# 18_Power_Management.net
KiCad netlist of a schematic drawn in Altium Designer
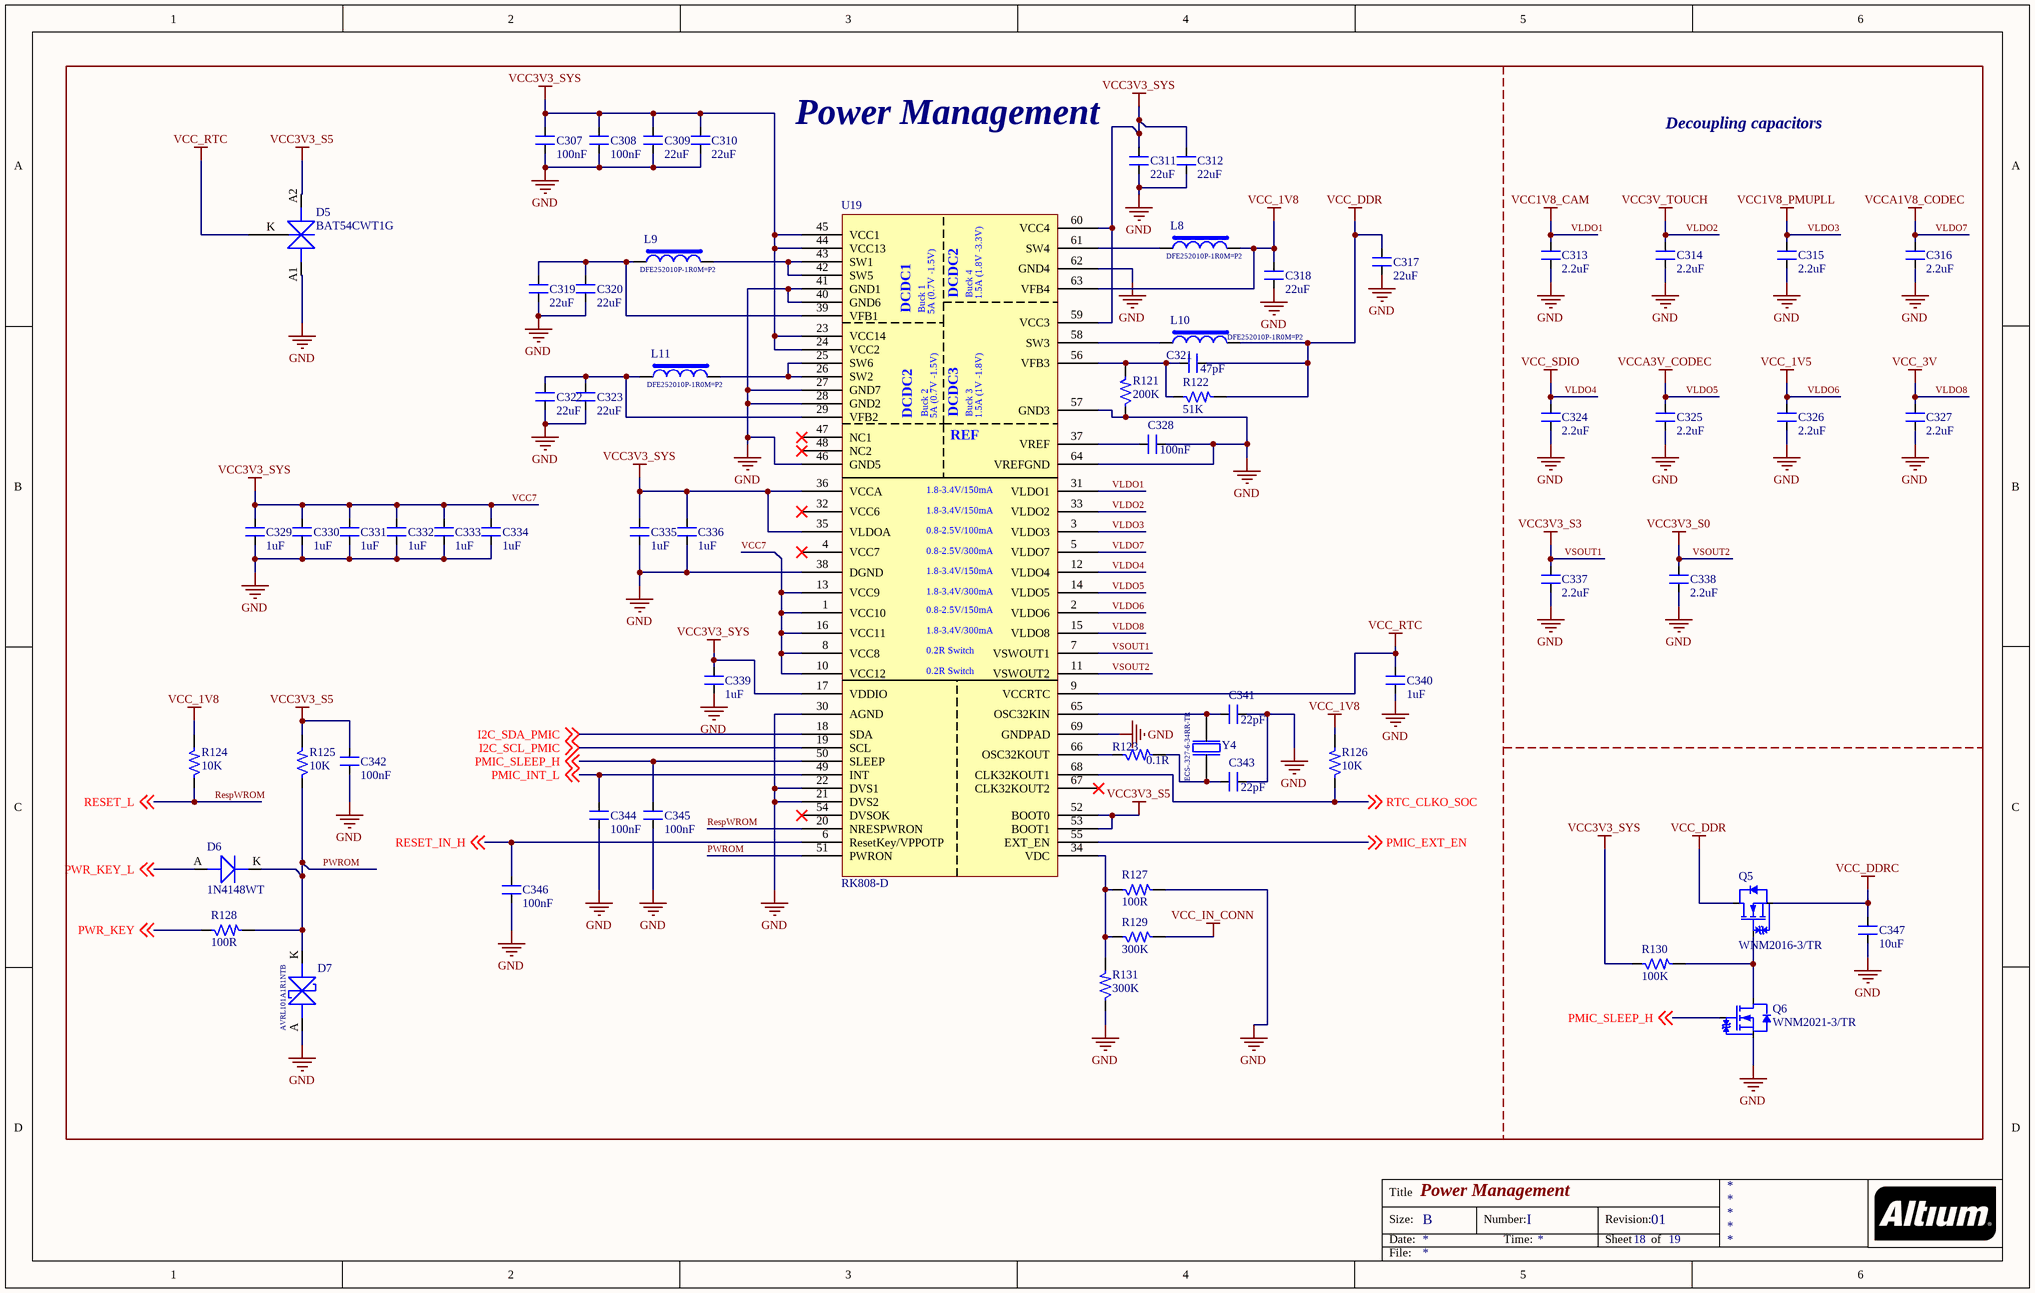
[diagram p0: [18] Power_Management.SchDoc]

(export (version "E")
  (design (tool "Eeschema 10.0.6"))
  (components
    (comp (ref "C307")
      (value "100nF")
      (footprint "CAP_0402")
      (description "0.1µF ±10% 25V Ceramic Capacitor X7R 0402 (1005 Metric)")
      (fields
        (field (name "MANUFACTURER") "Walsin Technology Corporation")
        (field (name "MANUFACTURER PART NUMBER") "0402B104K250CT")
      )
      (libsource (lib "EsteemPCB_SOM_Course_intlib") (part "CAP_100nF-25V-10%-0402"))
    )
    (comp (ref "C308")
      (value "100nF")
      (footprint "CAP_0402")
      (description "0.1µF ±10% 25V Ceramic Capacitor X7R 0402 (1005 Metric)")
      (fields
        (field (name "MANUFACTURER") "Walsin Technology Corporation")
        (field (name "MANUFACTURER PART NUMBER") "0402B104K250CT")
      )
      (libsource (lib "EsteemPCB_SOM_Course_intlib") (part "CAP_100nF-25V-10%-0402"))
    )
    (comp (ref "C309")
      (value "22uF")
      (footprint "CAP_0603")
      (description "22µF ±20% 10V Ceramic Capacitor X5R 0603 (1608 Metric)")
      (fields
        (field (name "MANUFACTURER") "Murata Electronics")
        (field (name "MANUFACTURER PART NUMBER") "GRM188R61A226ME15D")
      )
      (libsource (lib "EsteemPCB_SOM_Course_intlib") (part "CAP_22uF-10V-20%-0603"))
    )
    (comp (ref "C310")
      (value "22uF")
      (footprint "CAP_0603")
      (description "22µF ±20% 10V Ceramic Capacitor X5R 0603 (1608 Metric)")
      (fields
        (field (name "MANUFACTURER") "Murata Electronics")
        (field (name "MANUFACTURER PART NUMBER") "GRM188R61A226ME15D")
      )
      (libsource (lib "EsteemPCB_SOM_Course_intlib") (part "CAP_22uF-10V-20%-0603"))
    )
    (comp (ref "C311")
      (value "22uF")
      (footprint "CAP_0603")
      (description "22µF ±20% 10V Ceramic Capacitor X5R 0603 (1608 Metric)")
      (fields
        (field (name "MANUFACTURER") "Murata Electronics")
        (field (name "MANUFACTURER PART NUMBER") "GRM188R61A226ME15D")
      )
      (libsource (lib "EsteemPCB_SOM_Course_intlib") (part "CAP_22uF-10V-20%-0603"))
    )
    (comp (ref "C312")
      (value "22uF")
      (footprint "CAP_0603")
      (description "22µF ±20% 10V Ceramic Capacitor X5R 0603 (1608 Metric)")
      (fields
        (field (name "MANUFACTURER") "Murata Electronics")
        (field (name "MANUFACTURER PART NUMBER") "GRM188R61A226ME15D")
      )
      (libsource (lib "EsteemPCB_SOM_Course_intlib") (part "CAP_22uF-10V-20%-0603"))
    )
    (comp (ref "C313")
      (value "2.2uF")
      (footprint "CAP_0402")
      (description "2.2µF ±10% 10V Ceramic Capacitor X5R 0402 (1005 Metric)")
      (fields
        (field (name "MANUFACTURER") "Murata Electronics")
        (field (name "MANUFACTURER PART NUMBER") "GRM155R61A225KE95D")
      )
      (libsource (lib "EsteemPCB_SOM_Course_intlib") (part "CAP_2.2uF-10V-10%-0402"))
    )
    (comp (ref "C314")
      (value "2.2uF")
      (footprint "CAP_0402")
      (description "2.2µF ±10% 10V Ceramic Capacitor X5R 0402 (1005 Metric)")
      (fields
        (field (name "MANUFACTURER") "Murata Electronics")
        (field (name "MANUFACTURER PART NUMBER") "GRM155R61A225KE95D")
      )
      (libsource (lib "EsteemPCB_SOM_Course_intlib") (part "CAP_2.2uF-10V-10%-0402"))
    )
    (comp (ref "C315")
      (value "2.2uF")
      (footprint "CAP_0402")
      (description "2.2µF ±10% 10V Ceramic Capacitor X5R 0402 (1005 Metric)")
      (fields
        (field (name "MANUFACTURER") "Murata Electronics")
        (field (name "MANUFACTURER PART NUMBER") "GRM155R61A225KE95D")
      )
      (libsource (lib "EsteemPCB_SOM_Course_intlib") (part "CAP_2.2uF-10V-10%-0402"))
    )
    (comp (ref "C316")
      (value "2.2uF")
      (footprint "CAP_0402")
      (description "2.2µF ±10% 10V Ceramic Capacitor X5R 0402 (1005 Metric)")
      (fields
        (field (name "MANUFACTURER") "Murata Electronics")
        (field (name "MANUFACTURER PART NUMBER") "GRM155R61A225KE95D")
      )
      (libsource (lib "EsteemPCB_SOM_Course_intlib") (part "CAP_2.2uF-10V-10%-0402"))
    )
    (comp (ref "C317")
      (value "22uF")
      (footprint "CAP_0603")
      (description "22µF ±20% 10V Ceramic Capacitor X5R 0603 (1608 Metric)")
      (fields
        (field (name "MANUFACTURER") "Murata Electronics")
        (field (name "MANUFACTURER PART NUMBER") "GRM188R61A226ME15D")
      )
      (libsource (lib "EsteemPCB_SOM_Course_intlib") (part "CAP_22uF-10V-20%-0603"))
    )
    (comp (ref "C318")
      (value "22uF")
      (footprint "CAP_0603")
      (description "22µF ±20% 10V Ceramic Capacitor X5R 0603 (1608 Metric)")
      (fields
        (field (name "MANUFACTURER") "Murata Electronics")
        (field (name "MANUFACTURER PART NUMBER") "GRM188R61A226ME15D")
      )
      (libsource (lib "EsteemPCB_SOM_Course_intlib") (part "CAP_22uF-10V-20%-0603"))
    )
    (comp (ref "C319")
      (value "22uF")
      (footprint "CAP_0603")
      (description "22µF ±20% 10V Ceramic Capacitor X5R 0603 (1608 Metric)")
      (fields
        (field (name "MANUFACTURER") "Murata Electronics")
        (field (name "MANUFACTURER PART NUMBER") "GRM188R61A226ME15D")
      )
      (libsource (lib "EsteemPCB_SOM_Course_intlib") (part "CAP_22uF-10V-20%-0603"))
    )
    (comp (ref "C320")
      (value "22uF")
      (footprint "CAP_0603")
      (description "22µF ±20% 10V Ceramic Capacitor X5R 0603 (1608 Metric)")
      (fields
        (field (name "MANUFACTURER") "Murata Electronics")
        (field (name "MANUFACTURER PART NUMBER") "GRM188R61A226ME15D")
      )
      (libsource (lib "EsteemPCB_SOM_Course_intlib") (part "CAP_22uF-10V-20%-0603"))
    )
    (comp (ref "C321")
      (value "47pF")
      (footprint "CAP_0402")
      (description "47pF ±10% 10V Ceramic Capacitor C0G, NP0 0402 (1005 Metric)")
      (fields
        (field (name "MANUFACTURER") "KEMET")
        (field (name "MANUFACTURER PART NUMBER") "C0402C470K8GAC7867")
      )
      (libsource (lib "EsteemPCB_SOM_Course_intlib") (part "CAP_47pF-10V-10%-0402"))
    )
    (comp (ref "C322")
      (value "22uF")
      (footprint "CAP_0603")
      (description "22µF ±20% 10V Ceramic Capacitor X5R 0603 (1608 Metric)")
      (fields
        (field (name "MANUFACTURER") "Murata Electronics")
        (field (name "MANUFACTURER PART NUMBER") "GRM188R61A226ME15D")
      )
      (libsource (lib "EsteemPCB_SOM_Course_intlib") (part "CAP_22uF-10V-20%-0603"))
    )
    (comp (ref "C323")
      (value "22uF")
      (footprint "CAP_0603")
      (description "22µF ±20% 10V Ceramic Capacitor X5R 0603 (1608 Metric)")
      (fields
        (field (name "MANUFACTURER") "Murata Electronics")
        (field (name "MANUFACTURER PART NUMBER") "GRM188R61A226ME15D")
      )
      (libsource (lib "EsteemPCB_SOM_Course_intlib") (part "CAP_22uF-10V-20%-0603"))
    )
    (comp (ref "C324")
      (value "2.2uF")
      (footprint "CAP_0402")
      (description "2.2µF ±10% 10V Ceramic Capacitor X5R 0402 (1005 Metric)")
      (fields
        (field (name "MANUFACTURER") "Murata Electronics")
        (field (name "MANUFACTURER PART NUMBER") "GRM155R61A225KE95D")
      )
      (libsource (lib "EsteemPCB_SOM_Course_intlib") (part "CAP_2.2uF-10V-10%-0402"))
    )
    (comp (ref "C325")
      (value "2.2uF")
      (footprint "CAP_0402")
      (description "2.2µF ±10% 10V Ceramic Capacitor X5R 0402 (1005 Metric)")
      (fields
        (field (name "MANUFACTURER") "Murata Electronics")
        (field (name "MANUFACTURER PART NUMBER") "GRM155R61A225KE95D")
      )
      (libsource (lib "EsteemPCB_SOM_Course_intlib") (part "CAP_2.2uF-10V-10%-0402"))
    )
    (comp (ref "C326")
      (value "2.2uF")
      (footprint "CAP_0402")
      (description "2.2µF ±10% 10V Ceramic Capacitor X5R 0402 (1005 Metric)")
      (fields
        (field (name "MANUFACTURER") "Murata Electronics")
        (field (name "MANUFACTURER PART NUMBER") "GRM155R61A225KE95D")
      )
      (libsource (lib "EsteemPCB_SOM_Course_intlib") (part "CAP_2.2uF-10V-10%-0402"))
    )
    (comp (ref "C327")
      (value "2.2uF")
      (footprint "CAP_0402")
      (description "2.2µF ±10% 10V Ceramic Capacitor X5R 0402 (1005 Metric)")
      (fields
        (field (name "MANUFACTURER") "Murata Electronics")
        (field (name "MANUFACTURER PART NUMBER") "GRM155R61A225KE95D")
      )
      (libsource (lib "EsteemPCB_SOM_Course_intlib") (part "CAP_2.2uF-10V-10%-0402"))
    )
    (comp (ref "C328")
      (value "100nF")
      (footprint "CAP_0402")
      (description "0.1µF ±10% 10V Ceramic Capacitor X7R 0402 (1005 Metric)")
      (fields
        (field (name "MANUFACTURER") "Yageo")
        (field (name "MANUFACTURER PART NUMBER") "CC0402KRX7R6BB104")
      )
      (libsource (lib "EsteemPCB_SOM_Course_intlib") (part "CAP_100nF-10V-10%-0402"))
    )
    (comp (ref "C329")
      (value "1uF")
      (footprint "CAP_0402")
      (description "1µF ±10% 10V Ceramic Capacitor X6S 0402 (1005 Metric)")
      (fields
        (field (name "MANUFACTURER") "Murata Electronics")
        (field (name "MANUFACTURER PART NUMBER") "GRT155C81A105KE01D")
      )
      (libsource (lib "EsteemPCB_SOM_Course_intlib") (part "CAP_1uF-10V-10%-0402"))
    )
    (comp (ref "C330")
      (value "1uF")
      (footprint "CAP_0402")
      (description "1µF ±10% 10V Ceramic Capacitor X6S 0402 (1005 Metric)")
      (fields
        (field (name "MANUFACTURER") "Murata Electronics")
        (field (name "MANUFACTURER PART NUMBER") "GRT155C81A105KE01D")
      )
      (libsource (lib "EsteemPCB_SOM_Course_intlib") (part "CAP_1uF-10V-10%-0402"))
    )
    (comp (ref "C331")
      (value "1uF")
      (footprint "CAP_0402")
      (description "1µF ±10% 10V Ceramic Capacitor X6S 0402 (1005 Metric)")
      (fields
        (field (name "MANUFACTURER") "Murata Electronics")
        (field (name "MANUFACTURER PART NUMBER") "GRT155C81A105KE01D")
      )
      (libsource (lib "EsteemPCB_SOM_Course_intlib") (part "CAP_1uF-10V-10%-0402"))
    )
    (comp (ref "C332")
      (value "1uF")
      (footprint "CAP_0402")
      (description "1µF ±10% 10V Ceramic Capacitor X6S 0402 (1005 Metric)")
      (fields
        (field (name "MANUFACTURER") "Murata Electronics")
        (field (name "MANUFACTURER PART NUMBER") "GRT155C81A105KE01D")
      )
      (libsource (lib "EsteemPCB_SOM_Course_intlib") (part "CAP_1uF-10V-10%-0402"))
    )
    (comp (ref "C333")
      (value "1uF")
      (footprint "CAP_0402")
      (description "1µF ±10% 10V Ceramic Capacitor X6S 0402 (1005 Metric)")
      (fields
        (field (name "MANUFACTURER") "Murata Electronics")
        (field (name "MANUFACTURER PART NUMBER") "GRT155C81A105KE01D")
      )
      (libsource (lib "EsteemPCB_SOM_Course_intlib") (part "CAP_1uF-10V-10%-0402"))
    )
    (comp (ref "C334")
      (value "1uF")
      (footprint "CAP_0402")
      (description "1µF ±10% 10V Ceramic Capacitor X6S 0402 (1005 Metric)")
      (fields
        (field (name "MANUFACTURER") "Murata Electronics")
        (field (name "MANUFACTURER PART NUMBER") "GRT155C81A105KE01D")
      )
      (libsource (lib "EsteemPCB_SOM_Course_intlib") (part "CAP_1uF-10V-10%-0402"))
    )
    (comp (ref "C335")
      (value "1uF")
      (footprint "CAP_0402")
      (description "1µF ±10% 10V Ceramic Capacitor X6S 0402 (1005 Metric)")
      (fields
        (field (name "MANUFACTURER") "Murata Electronics")
        (field (name "MANUFACTURER PART NUMBER") "GRT155C81A105KE01D")
      )
      (libsource (lib "EsteemPCB_SOM_Course_intlib") (part "CAP_1uF-10V-10%-0402"))
    )
    (comp (ref "C336")
      (value "1uF")
      (footprint "CAP_0402")
      (description "1µF ±10% 10V Ceramic Capacitor X6S 0402 (1005 Metric)")
      (fields
        (field (name "MANUFACTURER") "Murata Electronics")
        (field (name "MANUFACTURER PART NUMBER") "GRT155C81A105KE01D")
      )
      (libsource (lib "EsteemPCB_SOM_Course_intlib") (part "CAP_1uF-10V-10%-0402"))
    )
    (comp (ref "C337")
      (value "2.2uF")
      (footprint "CAP_0402")
      (description "2.2µF ±10% 10V Ceramic Capacitor X5R 0402 (1005 Metric)")
      (fields
        (field (name "MANUFACTURER") "Murata Electronics")
        (field (name "MANUFACTURER PART NUMBER") "GRM155R61A225KE95D")
      )
      (libsource (lib "EsteemPCB_SOM_Course_intlib") (part "CAP_2.2uF-10V-10%-0402"))
    )
    (comp (ref "C338")
      (value "2.2uF")
      (footprint "CAP_0402")
      (description "2.2µF ±10% 10V Ceramic Capacitor X5R 0402 (1005 Metric)")
      (fields
        (field (name "MANUFACTURER") "Murata Electronics")
        (field (name "MANUFACTURER PART NUMBER") "GRM155R61A225KE95D")
      )
      (libsource (lib "EsteemPCB_SOM_Course_intlib") (part "CAP_2.2uF-10V-10%-0402"))
    )
    (comp (ref "C339")
      (value "1uF")
      (footprint "CAP_0402")
      (description "1µF ±10% 10V Ceramic Capacitor X6S 0402 (1005 Metric)")
      (fields
        (field (name "MANUFACTURER") "Murata Electronics")
        (field (name "MANUFACTURER PART NUMBER") "GRT155C81A105KE01D")
      )
      (libsource (lib "EsteemPCB_SOM_Course_intlib") (part "CAP_1uF-10V-10%-0402"))
    )
    (comp (ref "C340")
      (value "1uF")
      (footprint "CAP_0402")
      (description "1µF ±10% 16V Ceramic Capacitor X5R 0402 (1005 Metric)")
      (fields
        (field (name "MANUFACTURER") "Knowles Novacap")
        (field (name "MANUFACTURER PART NUMBER") "0402BW105K160YT")
      )
      (libsource (lib "EsteemPCB_SOM_Course_intlib") (part "CAP_1uF-16V-10%-0402"))
    )
    (comp (ref "C341")
      (value "22pF")
      (footprint "CAP_0402")
      (description "22pF ±10% 10V Ceramic Capacitor C0G, NP0 0402 (1005 Metric)")
      (fields
        (field (name "MANUFACTURER") "KEMET")
        (field (name "MANUFACTURER PART NUMBER") "C0402C220K8GACTU")
      )
      (libsource (lib "EsteemPCB_SOM_Course_intlib") (part "CAP_22pF-10V-10%-0402"))
    )
    (comp (ref "C342")
      (value "100nF")
      (footprint "CAP_0402")
      (description "0.1µF ±10% 10V Ceramic Capacitor X7R 0402 (1005 Metric)")
      (fields
        (field (name "MANUFACTURER") "Yageo")
        (field (name "MANUFACTURER PART NUMBER") "CC0402KRX7R6BB104")
      )
      (libsource (lib "EsteemPCB_SOM_Course_intlib") (part "CAP_100nF-10V-10%-0402"))
    )
    (comp (ref "C343")
      (value "22pF")
      (footprint "CAP_0402")
      (description "22pF ±10% 10V Ceramic Capacitor C0G, NP0 0402 (1005 Metric)")
      (fields
        (field (name "MANUFACTURER") "KEMET")
        (field (name "MANUFACTURER PART NUMBER") "C0402C220K8GACTU")
      )
      (libsource (lib "EsteemPCB_SOM_Course_intlib") (part "CAP_22pF-10V-10%-0402"))
    )
    (comp (ref "C344")
      (value "100nF")
      (footprint "CAP_0402")
      (description "0.1µF ±10% 10V Ceramic Capacitor X7R 0402 (1005 Metric)")
      (fields
        (field (name "MANUFACTURER") "Yageo")
        (field (name "MANUFACTURER PART NUMBER") "CC0402KRX7R6BB104")
      )
      (libsource (lib "EsteemPCB_SOM_Course_intlib") (part "CAP_100nF-10V-10%-0402"))
    )
    (comp (ref "C345")
      (value "100nF")
      (footprint "CAP_0402")
      (description "0.1µF ±10% 10V Ceramic Capacitor X7R 0402 (1005 Metric)")
      (fields
        (field (name "MANUFACTURER") "Yageo")
        (field (name "MANUFACTURER PART NUMBER") "CC0402KRX7R6BB104")
      )
      (libsource (lib "EsteemPCB_SOM_Course_intlib") (part "CAP_100nF-10V-10%-0402"))
    )
    (comp (ref "C346")
      (value "100nF")
      (footprint "CAP_0402")
      (description "0.1µF ±10% 10V Ceramic Capacitor X7R 0402 (1005 Metric)")
      (fields
        (field (name "MANUFACTURER") "Yageo")
        (field (name "MANUFACTURER PART NUMBER") "CC0402KRX7R6BB104")
      )
      (libsource (lib "EsteemPCB_SOM_Course_intlib") (part "CAP_100nF-10V-10%-0402"))
    )
    (comp (ref "C347")
      (value "10uF")
      (footprint "CAP_0402")
      (description "10µF ±20% 10V Ceramic Capacitor X5R 0402 (1005 Metric)")
      (fields
        (field (name "MANUFACTURER PART NUMBER") "CL05A106MP5NUNC")
        (field (name "MANUFACTURER") "Samsung Electro-Mechanics")
      )
      (libsource (lib "EsteemPCB_SOM_Course_intlib") (part "CAP_10uF-10V-20%-0402"))
    )
    (comp (ref "D5")
      (value "BAT54CWT1G")
      (footprint "DIO_SOT-323-3")
      (description "Diode Array 1 Pair Common Cathode Schottky 30V 200mA (DC) Surface Mount SC-70, SOT-323")
      (fields (field (name "MANUFACTURER") "ON Semiconductor"))
      (libsource (lib "EsteemPCB_SOM_Course_intlib") (part "DIO-S-A_30V-200mA-SOT-323"))
    )
    (comp (ref "D6")
      (value "1N4148WT")
      (footprint "DIO_SOD523")
      (description "Diode Standard 100V 300mA (DC) Surface Mount SOD-123")
      (fields (field (name "MANUFACTURER") "FAIRCHILD"))
      (libsource (lib "EsteemPCB_SOM_Course_intlib") (part "DIO_75V-200mA-SOD-523F"))
    )
    (comp (ref "D7")
      (value "AVRL101A1R1NTB")
      (footprint "DIO_0402_SMD")
      (description "39V Varistor 1 Circuit Surface Mount, MLCV 0402 (1005 Metric)")
      (fields (field (name "MANUFACTURER") "TDK Corporation"))
      (libsource (lib "EsteemPCB_SOM_Course_intlib") (part "DIO-T_10V-39V-0402"))
    )
    (comp (ref "L8")
      (value "DFE252010P-1R0M=P2")
      (footprint "IND_1008")
      (description "1µH Shielded Wirewound Inductor 3.8A 54mOhm Max 1008 (2520 Metric)")
      (fields (field (name "MANUFACTURER") "Murata Electronics"))
      (libsource (lib "EsteemPCB_SOM_Course_intlib") (part "IND_1uH-3.8A-20%-1008"))
    )
    (comp (ref "L9")
      (value "DFE252010P-1R0M=P2")
      (footprint "IND_1008")
      (description "1µH Shielded Wirewound Inductor 3.8A 54mOhm Max 1008 (2520 Metric)")
      (fields (field (name "MANUFACTURER") "Murata Electronics"))
      (libsource (lib "EsteemPCB_SOM_Course_intlib") (part "IND_1uH-3.8A-20%-1008"))
    )
    (comp (ref "L10")
      (value "DFE252010P-1R0M=P2")
      (footprint "IND_1008")
      (description "1µH Shielded Wirewound Inductor 3.8A 54mOhm Max 1008 (2520 Metric)")
      (fields (field (name "MANUFACTURER") "Murata Electronics"))
      (libsource (lib "EsteemPCB_SOM_Course_intlib") (part "IND_1uH-3.8A-20%-1008"))
    )
    (comp (ref "L11")
      (value "DFE252010P-1R0M=P2")
      (footprint "IND_1008")
      (description "1µH Shielded Wirewound Inductor 3.8A 54mOhm Max 1008 (2520 Metric)")
      (fields (field (name "MANUFACTURER") "Murata Electronics"))
      (libsource (lib "EsteemPCB_SOM_Course_intlib") (part "IND_1uH-3.8A-20%-1008"))
    )
    (comp (ref "Q5")
      (value "WNM2016-3/TR")
      (footprint "SOT 23-3")
      (description "N Channel 20V 2.9A 1V @ 250uA 47mΩ @ 3.6A,4.5V 700mW SOT-23(SOT-23-3) MOSFET RoHS")
      (fields (field (name "MANUFACTURER") "WILLSEMI(Will Semicon)"))
      (libsource (lib "EsteemPCB_SOM_Course_intlib") (part "MOSFET-N_20V-2.9A-SOT-23"))
    )
    (comp (ref "Q6")
      (value "WNM2021-3/TR")
      (footprint "SOT-323-3")
      (description "N Channel 20V 820mA 850mV @ 250uA 310mΩ @ 550mA,4.5V 310mW SOT-323(SC-70) MOSFET RoHS")
      (fields (field (name "MANUFACTURER") "WILLSEMI(Will Semicon)"))
      (libsource (lib "EsteemPCB_SOM_Course_intlib") (part "MOSFET-N_20V-820mA-SOT-323"))
    )
    (comp (ref "R121")
      (value "200K")
      (footprint "RES_0402")
      (description "200 kOhms ±1% 0.1W, 1/10W Chip Resistor 0402 (1005 Metric) Automotive AEC-Q200 Thick Film")
      (fields
        (field (name "MANUFACTURER") "Panasonic Electronic Components")
        (field (name "MANUFACTURER PART NUMBER") "ERJ-2RKF2003X")
      )
      (libsource (lib "EsteemPCB_SOM_Course_intlib") (part "RES_200K-0.1W-1%-0402"))
    )
    (comp (ref "R122")
      (value "51K")
      (footprint "RES_0402")
      (description "51 kOhms ±1% 0.1W, 1/10W Chip Resistor 0402 (1005 Metric) Automotive AEC-Q200 Thick Film")
      (fields
        (field (name "MANUFACTURER") "Panasonic Electronic Components")
        (field (name "MANUFACTURER PART NUMBER") "ERJ-2RKF5102X")
      )
      (libsource (lib "EsteemPCB_SOM_Course_intlib") (part "RES_51K-0.1W-1%-0402"))
    )
    (comp (ref "R123")
      (value "0.1R")
      (footprint "RES_0402")
      (fields
        (field (name "MANUFACTURER") "Samsung Electro-Mechanics")
        (field (name "MANUFACTURER PART NUMBER") "RUT1005FR100CS")
      )
      (libsource (lib "EsteemPCB_SOM_Course_intlib") (part "RES_0.1R-0.1W-1%-0402"))
    )
    (comp (ref "R124")
      (value "10K")
      (footprint "RES_0402")
      (description "10 kOhms ±1% 0.1W, 1/10W Chip Resistor 0402 (1005 Metric) Anti-Sulfur Thin Film")
      (fields
        (field (name "MANUFACTURER") "Vishay Beyschlag/Draloric/BC Components")
        (field (name "MANUFACTURER PART NUMBER") "MCS04020C1002FE000")
      )
      (libsource (lib "EsteemPCB_SOM_Course_intlib") (part "RES_10K-0.1W-1%-0402"))
    )
    (comp (ref "R125")
      (value "10K")
      (footprint "RES_0402")
      (description "10 kOhms ±1% 0.1W, 1/10W Chip Resistor 0402 (1005 Metric) Anti-Sulfur Thin Film")
      (fields
        (field (name "MANUFACTURER") "Vishay Beyschlag/Draloric/BC Components")
        (field (name "MANUFACTURER PART NUMBER") "MCS04020C1002FE000")
      )
      (libsource (lib "EsteemPCB_SOM_Course_intlib") (part "RES_10K-0.1W-1%-0402"))
    )
    (comp (ref "R126")
      (value "10K")
      (footprint "RES_0402")
      (description "10 kOhms ±1% 0.1W, 1/10W Chip Resistor 0402 (1005 Metric) Anti-Sulfur Thin Film")
      (fields
        (field (name "MANUFACTURER") "Vishay Beyschlag/Draloric/BC Components")
        (field (name "MANUFACTURER PART NUMBER") "MCS04020C1002FE000")
      )
      (libsource (lib "EsteemPCB_SOM_Course_intlib") (part "RES_10K-0.1W-1%-0402"))
    )
    (comp (ref "R127")
      (value "100R")
      (footprint "RES_0402")
      (fields
        (field (name "MANUFACTURER") "KOA Speer Electronics, Inc.")
        (field (name "MANUFACTURER PART NUMBER") "RK73H1ETTP1000F")
      )
      (libsource (lib "EsteemPCB_SOM_Course_intlib") (part "RES_100R-0.1W-1%-0402"))
    )
    (comp (ref "R128")
      (value "100R")
      (footprint "RES_0402")
      (fields
        (field (name "MANUFACTURER") "KOA Speer Electronics, Inc.")
        (field (name "MANUFACTURER PART NUMBER") "RK73H1ETTP1000F")
      )
      (libsource (lib "EsteemPCB_SOM_Course_intlib") (part "RES_100R-0.1W-1%-0402"))
    )
    (comp (ref "R129")
      (value "300K")
      (footprint "RES_0402")
      (description "300 kOhms ±1% 0.1W, 1/10W Chip Resistor 0402 (1005 Metric) Automotive AEC-Q200 Thick Film")
      (fields
        (field (name "MANUFACTURER") "Panasonic Electronic Components")
        (field (name "MANUFACTURER PART NUMBER") "ERJ-2RKF3003X")
      )
      (libsource (lib "EsteemPCB_SOM_Course_intlib") (part "RES_300K-0.1W-1%-0402"))
    )
    (comp (ref "R130")
      (value "100K")
      (footprint "RES_0402")
      (description "100 kOhms ±1% 0.1W, 1/10W Chip Resistor 0402 (1005 Metric) Anti-Sulfur Thin Film")
      (fields
        (field (name "MANUFACTURER") "Vishay Beyschlag/Draloric/BC Components")
        (field (name "MANUFACTURER PART NUMBER") "MCS04020C1003FE000")
      )
      (libsource (lib "EsteemPCB_SOM_Course_intlib") (part "RES_100K-0.1W-1%-0402"))
    )
    (comp (ref "R131")
      (value "300K")
      (footprint "RES_0402")
      (description "300 kOhms ±1% 0.1W, 1/10W Chip Resistor 0402 (1005 Metric) Automotive AEC-Q200 Thick Film")
      (fields
        (field (name "MANUFACTURER") "Panasonic Electronic Components")
        (field (name "MANUFACTURER PART NUMBER") "ERJ-2RKF3003X")
      )
      (libsource (lib "EsteemPCB_SOM_Course_intlib") (part "RES_300K-0.1W-1%-0402"))
    )
    (comp (ref "U19")
      (value "RK808-D")
      (footprint "QFN68_13.7_220.4X220.4_SMD")
      (description "The RK808 is a complete power supply solution for Portable systems.")
      (fields (field (name "MANUFACTURER") "Rockchip"))
      (libsource (lib "EsteemPCB_SOM_Course_intlib") (part "IC_RK808-D-QFN68"))
    )
    (comp (ref "Y4")
      (value "ECS-.327-6-34RR-TR")
      (footprint "XTAL_ECS-.327-6-34RR-TR")
      (description "32.768kHz ±20ppm Crystal 12pF 80 kOhms 2-SMD, No Lead")
      (fields (field (name "MANUFACTURER") "Ecliptek"))
      (libsource (lib "EsteemPCB_SOM_Course_intlib") (part "XTAL_32.768Khz-22pF-SMD"))
    )
  )
  (nets
    (net (code "1") (name "/PWROM") (class "Default")
      (node (ref "D6") (pin "K") (pinfunction "CATHODE_K") (pintype "passive"))
      (node (ref "D7") (pin "K") (pinfunction "K_K") (pintype "passive"))
      (node (ref "R125") (pin "1") (pinfunction "1_1") (pintype "passive"))
      (node (ref "R128") (pin "2") (pinfunction "2_2") (pintype "passive"))
      (node (ref "U19") (pin "51") (pinfunction "PWRON_51") (pintype "passive"))
    )
    (net (code "2") (name "GND") (class "Default")
      (node (ref "C307") (pin "1") (pinfunction "1_1") (pintype "passive"))
      (node (ref "C308") (pin "1") (pinfunction "1_1") (pintype "passive"))
      (node (ref "C309") (pin "1") (pinfunction "1_1") (pintype "passive"))
      (node (ref "C310") (pin "1") (pinfunction "1_1") (pintype "passive"))
      (node (ref "C311") (pin "1") (pinfunction "1_1") (pintype "passive"))
      (node (ref "C312") (pin "1") (pinfunction "1_1") (pintype "passive"))
      (node (ref "C313") (pin "1") (pinfunction "1_1") (pintype "passive"))
      (node (ref "C314") (pin "1") (pinfunction "1_1") (pintype "passive"))
      (node (ref "C315") (pin "1") (pinfunction "1_1") (pintype "passive"))
      (node (ref "C316") (pin "1") (pinfunction "1_1") (pintype "passive"))
      (node (ref "C317") (pin "1") (pinfunction "1_1") (pintype "passive"))
      (node (ref "C318") (pin "1") (pinfunction "1_1") (pintype "passive"))
      (node (ref "C319") (pin "1") (pinfunction "1_1") (pintype "passive"))
      (node (ref "C320") (pin "1") (pinfunction "1_1") (pintype "passive"))
      (node (ref "C322") (pin "1") (pinfunction "1_1") (pintype "passive"))
      (node (ref "C323") (pin "1") (pinfunction "1_1") (pintype "passive"))
      (node (ref "C324") (pin "1") (pinfunction "1_1") (pintype "passive"))
      (node (ref "C325") (pin "1") (pinfunction "1_1") (pintype "passive"))
      (node (ref "C326") (pin "1") (pinfunction "1_1") (pintype "passive"))
      (node (ref "C327") (pin "1") (pinfunction "1_1") (pintype "passive"))
      (node (ref "C328") (pin "2") (pinfunction "2_2") (pintype "passive"))
      (node (ref "C329") (pin "1") (pinfunction "1_1") (pintype "passive"))
      (node (ref "C330") (pin "1") (pinfunction "1_1") (pintype "passive"))
      (node (ref "C331") (pin "1") (pinfunction "1_1") (pintype "passive"))
      (node (ref "C332") (pin "1") (pinfunction "1_1") (pintype "passive"))
      (node (ref "C333") (pin "1") (pinfunction "1_1") (pintype "passive"))
      (node (ref "C334") (pin "1") (pinfunction "1_1") (pintype "passive"))
      (node (ref "C335") (pin "1") (pinfunction "1_1") (pintype "passive"))
      (node (ref "C336") (pin "1") (pinfunction "1_1") (pintype "passive"))
      (node (ref "C337") (pin "1") (pinfunction "1_1") (pintype "passive"))
      (node (ref "C338") (pin "1") (pinfunction "1_1") (pintype "passive"))
      (node (ref "C339") (pin "1") (pinfunction "1_1") (pintype "passive"))
      (node (ref "C340") (pin "1") (pinfunction "1_1") (pintype "passive"))
      (node (ref "C341") (pin "2") (pinfunction "2_2") (pintype "passive"))
      (node (ref "C342") (pin "1") (pinfunction "1_1") (pintype "passive"))
      (node (ref "C343") (pin "2") (pinfunction "2_2") (pintype "passive"))
      (node (ref "C344") (pin "1") (pinfunction "1_1") (pintype "passive"))
      (node (ref "C345") (pin "1") (pinfunction "1_1") (pintype "passive"))
      (node (ref "C346") (pin "1") (pinfunction "1_1") (pintype "passive"))
      (node (ref "C347") (pin "1") (pinfunction "1_1") (pintype "passive"))
      (node (ref "D5") (pin "A1") (pinfunction "A1_A1") (pintype "passive"))
      (node (ref "D7") (pin "A") (pinfunction "A_A") (pintype "passive"))
      (node (ref "Q6") (pin "2") (pinfunction "S_2") (pintype "passive"))
      (node (ref "R121") (pin "1") (pinfunction "1_1") (pintype "passive"))
      (node (ref "R127") (pin "2") (pinfunction "2_2") (pintype "passive"))
      (node (ref "R131") (pin "1") (pinfunction "1_1") (pintype "passive"))
      (node (ref "U19") (pin "21") (pinfunction "DVS2_21") (pintype "passive"))
      (node (ref "U19") (pin "22") (pinfunction "DVS1_22") (pintype "passive"))
      (node (ref "U19") (pin "27") (pinfunction "GND7_27") (pintype "passive"))
      (node (ref "U19") (pin "28") (pinfunction "GND2_28") (pintype "passive"))
      (node (ref "U19") (pin "30") (pinfunction "AGND_30") (pintype "passive"))
      (node (ref "U19") (pin "38") (pinfunction "DGND_38") (pintype "passive"))
      (node (ref "U19") (pin "40") (pinfunction "GND6_40") (pintype "passive"))
      (node (ref "U19") (pin "41") (pinfunction "GND1_41") (pintype "passive"))
      (node (ref "U19") (pin "46") (pinfunction "GND5_46") (pintype "passive"))
      (node (ref "U19") (pin "57") (pinfunction "GND3_57") (pintype "passive"))
      (node (ref "U19") (pin "62") (pinfunction "GND4_62") (pintype "passive"))
      (node (ref "U19") (pin "64") (pinfunction "VREFGND_64") (pintype "passive"))
      (node (ref "U19") (pin "69") (pinfunction "GNDPAD_69") (pintype "passive"))
    )
    (net (code "3") (name "I2C_SCL_PMIC") (class "Default")
      (node (ref "U19") (pin "19") (pinfunction "SCL_19") (pintype "passive"))
    )
    (net (code "4") (name "I2C_SDA_PMIC") (class "Default")
      (node (ref "U19") (pin "18") (pinfunction "SDA_18") (pintype "passive"))
    )
    (net (code "5") (name "Net-(C343-Pad1)") (class "Default")
      (node (ref "C343") (pin "1") (pinfunction "1_1") (pintype "passive"))
      (node (ref "R123") (pin "2") (pinfunction "2_2") (pintype "passive"))
      (node (ref "Y4") (pin "1") (pinfunction "1_1") (pintype "passive"))
    )
    (net (code "6") (name "Net-(Q5-G)") (class "Default")
      (node (ref "Q5") (pin "1") (pinfunction "G_1") (pintype "passive"))
      (node (ref "Q6") (pin "3") (pinfunction "D_3") (pintype "passive"))
      (node (ref "R130") (pin "2") (pinfunction "2_2") (pintype "passive"))
    )
    (net (code "7") (name "Net-(U19-OSC32KIN)") (class "Default")
      (node (ref "C341") (pin "1") (pinfunction "1_1") (pintype "passive"))
      (node (ref "U19") (pin "65") (pinfunction "OSC32KIN_65") (pintype "passive"))
      (node (ref "Y4") (pin "2") (pinfunction "2_2") (pintype "passive"))
    )
    (net (code "8") (name "Net-(U19-OSC32KOUT)") (class "Default")
      (node (ref "R123") (pin "1") (pinfunction "1_1") (pintype "passive"))
      (node (ref "U19") (pin "66") (pinfunction "OSC32KOUT_66") (pintype "passive"))
    )
    (net (code "9") (name "Net-(U19-SW1)") (class "Default")
      (node (ref "L9") (pin "2") (pinfunction "2_2") (pintype "passive"))
      (node (ref "U19") (pin "42") (pinfunction "SW5_42") (pintype "passive"))
      (node (ref "U19") (pin "43") (pinfunction "SW1_43") (pintype "passive"))
    )
    (net (code "10") (name "Net-(U19-SW2)") (class "Default")
      (node (ref "L11") (pin "2") (pinfunction "2_2") (pintype "passive"))
      (node (ref "U19") (pin "25") (pinfunction "SW6_25") (pintype "passive"))
      (node (ref "U19") (pin "26") (pinfunction "SW2_26") (pintype "passive"))
    )
    (net (code "11") (name "Net-(U19-SW3)") (class "Default")
      (node (ref "L10") (pin "1") (pinfunction "1_1") (pintype "passive"))
      (node (ref "U19") (pin "58") (pinfunction "SW3_58") (pintype "passive"))
    )
    (net (code "12") (name "Net-(U19-SW4)") (class "Default")
      (node (ref "L8") (pin "1") (pinfunction "1_1") (pintype "passive"))
      (node (ref "U19") (pin "61") (pinfunction "SW4_61") (pintype "passive"))
    )
    (net (code "13") (name "Net-(U19-VDC)") (class "Default")
      (node (ref "R127") (pin "1") (pinfunction "1_1") (pintype "passive"))
      (node (ref "R129") (pin "1") (pinfunction "1_1") (pintype "passive"))
      (node (ref "R131") (pin "2") (pinfunction "2_2") (pintype "passive"))
      (node (ref "U19") (pin "34") (pinfunction "VDC_34") (pintype "passive"))
    )
    (net (code "14") (name "Net-(U19-VFB1)") (class "Default")
      (node (ref "C319") (pin "2") (pinfunction "2_2") (pintype "passive"))
      (node (ref "C320") (pin "2") (pinfunction "2_2") (pintype "passive"))
      (node (ref "L9") (pin "1") (pinfunction "1_1") (pintype "passive"))
      (node (ref "U19") (pin "39") (pinfunction "VFB1_39") (pintype "passive"))
    )
    (net (code "15") (name "Net-(U19-VFB2)") (class "Default")
      (node (ref "C322") (pin "2") (pinfunction "2_2") (pintype "passive"))
      (node (ref "C323") (pin "2") (pinfunction "2_2") (pintype "passive"))
      (node (ref "L11") (pin "1") (pinfunction "1_1") (pintype "passive"))
      (node (ref "U19") (pin "29") (pinfunction "VFB2_29") (pintype "passive"))
    )
    (net (code "16") (name "Net-(U19-VFB3)") (class "Default")
      (node (ref "C321") (pin "1") (pinfunction "1_1") (pintype "passive"))
      (node (ref "R121") (pin "2") (pinfunction "2_2") (pintype "passive"))
      (node (ref "R122") (pin "1") (pinfunction "1_1") (pintype "passive"))
      (node (ref "U19") (pin "56") (pinfunction "VFB3_56") (pintype "passive"))
    )
    (net (code "17") (name "Net-(U19-VREF)") (class "Default")
      (node (ref "C328") (pin "1") (pinfunction "1_1") (pintype "passive"))
      (node (ref "U19") (pin "37") (pinfunction "VREF_37") (pintype "passive"))
    )
    (net (code "18") (name "PMIC_EXT_EN") (class "Default")
      (node (ref "U19") (pin "55") (pinfunction "EXT_EN_55") (pintype "passive"))
    )
    (net (code "19") (name "PMIC_INT_L") (class "Default")
      (node (ref "C344") (pin "2") (pinfunction "2_2") (pintype "passive"))
      (node (ref "U19") (pin "49") (pinfunction "INT_49") (pintype "passive"))
    )
    (net (code "20") (name "PMIC_SLEEP_H") (class "Default")
      (node (ref "C345") (pin "2") (pinfunction "2_2") (pintype "passive"))
      (node (ref "Q6") (pin "1") (pinfunction "G_1") (pintype "passive"))
      (node (ref "U19") (pin "50") (pinfunction "SLEEP_50") (pintype "passive"))
    )
    (net (code "21") (name "PWR_KEY") (class "Default")
      (node (ref "R128") (pin "1") (pinfunction "1_1") (pintype "passive"))
    )
    (net (code "22") (name "PWR_KEY_L") (class "Default")
      (node (ref "D6") (pin "A") (pinfunction "ANODE_A") (pintype "passive"))
    )
    (net (code "23") (name "RESET_IN_H") (class "Default")
      (node (ref "C346") (pin "2") (pinfunction "2_2") (pintype "passive"))
      (node (ref "U19") (pin "6") (pinfunction "ResetKey/VPPOTP_6") (pintype "passive"))
    )
    (net (code "24") (name "RESET_L") (class "Default")
      (node (ref "R124") (pin "1") (pinfunction "1_1") (pintype "passive"))
      (node (ref "U19") (pin "20") (pinfunction "NRESPWRON_20") (pintype "passive"))
    )
    (net (code "25") (name "RTC_CLKO_SOC") (class "Default")
      (node (ref "R126") (pin "1") (pinfunction "1_1") (pintype "passive"))
      (node (ref "U19") (pin "68") (pinfunction "CLK32KOUT1_68") (pintype "passive"))
    )
    (net (code "26") (name "VCC1V8_CAM") (class "Default")
      (node (ref "C313") (pin "2") (pinfunction "2_2") (pintype "passive"))
      (node (ref "U19") (pin "31") (pinfunction "VLDO1_31") (pintype "passive"))
    )
    (net (code "27") (name "VCC1V8_PMUPLL") (class "Default")
      (node (ref "C315") (pin "2") (pinfunction "2_2") (pintype "passive"))
      (node (ref "U19") (pin "3") (pinfunction "VLDO3_3") (pintype "passive"))
    )
    (net (code "28") (name "VCC3V3_S0") (class "Default")
      (node (ref "C338") (pin "2") (pinfunction "2_2") (pintype "passive"))
      (node (ref "U19") (pin "11") (pinfunction "VSWOUT2_11") (pintype "passive"))
    )
    (net (code "29") (name "VCC3V3_S3") (class "Default")
      (node (ref "C337") (pin "2") (pinfunction "2_2") (pintype "passive"))
      (node (ref "U19") (pin "7") (pinfunction "VSWOUT1_7") (pintype "passive"))
    )
    (net (code "30") (name "VCC3V3_S5") (class "Default")
      (node (ref "C342") (pin "2") (pinfunction "2_2") (pintype "passive"))
      (node (ref "D5") (pin "A2") (pinfunction "A2_A2") (pintype "passive"))
      (node (ref "R125") (pin "2") (pinfunction "2_2") (pintype "passive"))
      (node (ref "U19") (pin "52") (pinfunction "BOOT0_52") (pintype "passive"))
      (node (ref "U19") (pin "53") (pinfunction "BOOT1_53") (pintype "passive"))
    )
    (net (code "31") (name "VCC3V3_SYS") (class "Default")
      (node (ref "C307") (pin "2") (pinfunction "2_2") (pintype "passive"))
      (node (ref "C308") (pin "2") (pinfunction "2_2") (pintype "passive"))
      (node (ref "C309") (pin "2") (pinfunction "2_2") (pintype "passive"))
      (node (ref "C310") (pin "2") (pinfunction "2_2") (pintype "passive"))
      (node (ref "C311") (pin "2") (pinfunction "2_2") (pintype "passive"))
      (node (ref "C312") (pin "2") (pinfunction "2_2") (pintype "passive"))
      (node (ref "C329") (pin "2") (pinfunction "2_2") (pintype "passive"))
      (node (ref "C330") (pin "2") (pinfunction "2_2") (pintype "passive"))
      (node (ref "C331") (pin "2") (pinfunction "2_2") (pintype "passive"))
      (node (ref "C332") (pin "2") (pinfunction "2_2") (pintype "passive"))
      (node (ref "C333") (pin "2") (pinfunction "2_2") (pintype "passive"))
      (node (ref "C334") (pin "2") (pinfunction "2_2") (pintype "passive"))
      (node (ref "C335") (pin "2") (pinfunction "2_2") (pintype "passive"))
      (node (ref "C336") (pin "2") (pinfunction "2_2") (pintype "passive"))
      (node (ref "C339") (pin "2") (pinfunction "2_2") (pintype "passive"))
      (node (ref "R130") (pin "1") (pinfunction "1_1") (pintype "passive"))
      (node (ref "U19") (pin "1") (pinfunction "VCC10_1") (pintype "passive"))
      (node (ref "U19") (pin "10") (pinfunction "VCC12_10") (pintype "passive"))
      (node (ref "U19") (pin "13") (pinfunction "VCC9_13") (pintype "passive"))
      (node (ref "U19") (pin "16") (pinfunction "VCC11_16") (pintype "passive"))
      (node (ref "U19") (pin "17") (pinfunction "VDDIO_17") (pintype "passive"))
      (node (ref "U19") (pin "23") (pinfunction "VCC14_23") (pintype "passive"))
      (node (ref "U19") (pin "24") (pinfunction "VCC2_24") (pintype "passive"))
      (node (ref "U19") (pin "35") (pinfunction "VLDOA_35") (pintype "passive"))
      (node (ref "U19") (pin "36") (pinfunction "VCCA_36") (pintype "passive"))
      (node (ref "U19") (pin "44") (pinfunction "VCC13_44") (pintype "passive"))
      (node (ref "U19") (pin "45") (pinfunction "VCC1_45") (pintype "passive"))
      (node (ref "U19") (pin "59") (pinfunction "VCC3_59") (pintype "passive"))
      (node (ref "U19") (pin "60") (pinfunction "VCC4_60") (pintype "passive"))
      (node (ref "U19") (pin "8") (pinfunction "VCC8_8") (pintype "passive"))
    )
    (net (code "32") (name "VCC3V_TOUCH") (class "Default")
      (node (ref "C314") (pin "2") (pinfunction "2_2") (pintype "passive"))
      (node (ref "U19") (pin "33") (pinfunction "VLDO2_33") (pintype "passive"))
    )
    (net (code "33") (name "VCCA1V8_CODEC") (class "Default")
      (node (ref "C316") (pin "2") (pinfunction "2_2") (pintype "passive"))
      (node (ref "U19") (pin "5") (pinfunction "VLDO7_5") (pintype "passive"))
    )
    (net (code "34") (name "VCCA3V_CODEC") (class "Default")
      (node (ref "C325") (pin "2") (pinfunction "2_2") (pintype "passive"))
      (node (ref "U19") (pin "14") (pinfunction "VLDO5_14") (pintype "passive"))
    )
    (net (code "35") (name "VCC_1V5") (class "Default")
      (node (ref "C326") (pin "2") (pinfunction "2_2") (pintype "passive"))
      (node (ref "U19") (pin "2") (pinfunction "VLDO6_2") (pintype "passive"))
    )
    (net (code "36") (name "VCC_1V8") (class "Default")
      (node (ref "C318") (pin "2") (pinfunction "2_2") (pintype "passive"))
      (node (ref "L8") (pin "2") (pinfunction "2_2") (pintype "passive"))
      (node (ref "R124") (pin "2") (pinfunction "2_2") (pintype "passive"))
      (node (ref "R126") (pin "2") (pinfunction "2_2") (pintype "passive"))
      (node (ref "U19") (pin "63") (pinfunction "VFB4_63") (pintype "passive"))
    )
    (net (code "37") (name "VCC_3V") (class "Default")
      (node (ref "C327") (pin "2") (pinfunction "2_2") (pintype "passive"))
      (node (ref "U19") (pin "15") (pinfunction "VLDO8_15") (pintype "passive"))
    )
    (net (code "38") (name "VCC_DDR") (class "Default")
      (node (ref "C317") (pin "2") (pinfunction "2_2") (pintype "passive"))
      (node (ref "C321") (pin "2") (pinfunction "2_2") (pintype "passive"))
      (node (ref "L10") (pin "2") (pinfunction "2_2") (pintype "passive"))
      (node (ref "Q5") (pin "3") (pinfunction "D_3") (pintype "passive"))
      (node (ref "R122") (pin "2") (pinfunction "2_2") (pintype "passive"))
    )
    (net (code "39") (name "VCC_DDRC") (class "Default")
      (node (ref "C347") (pin "2") (pinfunction "2_2") (pintype "passive"))
      (node (ref "Q5") (pin "2") (pinfunction "S_2") (pintype "passive"))
    )
    (net (code "40") (name "VCC_IN_CONN") (class "Default")
      (node (ref "R129") (pin "2") (pinfunction "2_2") (pintype "passive"))
    )
    (net (code "41") (name "VCC_RTC") (class "Default")
      (node (ref "C340") (pin "2") (pinfunction "2_2") (pintype "passive"))
      (node (ref "D5") (pin "K") (pinfunction "K_K") (pintype "passive"))
      (node (ref "U19") (pin "9") (pinfunction "VCCRTC_9") (pintype "passive"))
    )
    (net (code "42") (name "VCC_SDIO") (class "Default")
      (node (ref "C324") (pin "2") (pinfunction "2_2") (pintype "passive"))
      (node (ref "U19") (pin "12") (pinfunction "VLDO4_12") (pintype "passive"))
    )
    (net (code "43") (name "unconnected-(U19-CLK32KOUT2-Pad67)") (class "Default")
      (node (ref "U19") (pin "67") (pinfunction "CLK32KOUT2_67") (pintype "passive+no_connect"))
    )
    (net (code "44") (name "unconnected-(U19-DVSOK-Pad54)") (class "Default")
      (node (ref "U19") (pin "54") (pinfunction "DVSOK_54") (pintype "passive+no_connect"))
    )
    (net (code "45") (name "unconnected-(U19-NC1-Pad47)") (class "Default")
      (node (ref "U19") (pin "47") (pinfunction "NC1_47") (pintype "passive+no_connect"))
    )
    (net (code "46") (name "unconnected-(U19-NC2-Pad48)") (class "Default")
      (node (ref "U19") (pin "48") (pinfunction "NC2_48") (pintype "passive+no_connect"))
    )
    (net (code "47") (name "unconnected-(U19-VCC6-Pad32)") (class "Default")
      (node (ref "U19") (pin "32") (pinfunction "VCC6_32") (pintype "passive+no_connect"))
    )
    (net (code "48") (name "unconnected-(U19-VCC7-Pad4)") (class "Default")
      (node (ref "U19") (pin "4") (pinfunction "VCC7_4") (pintype "passive+no_connect"))
    )
  )
)
